# JVS.net
KiCad netlist of a schematic drawn in EAGLE
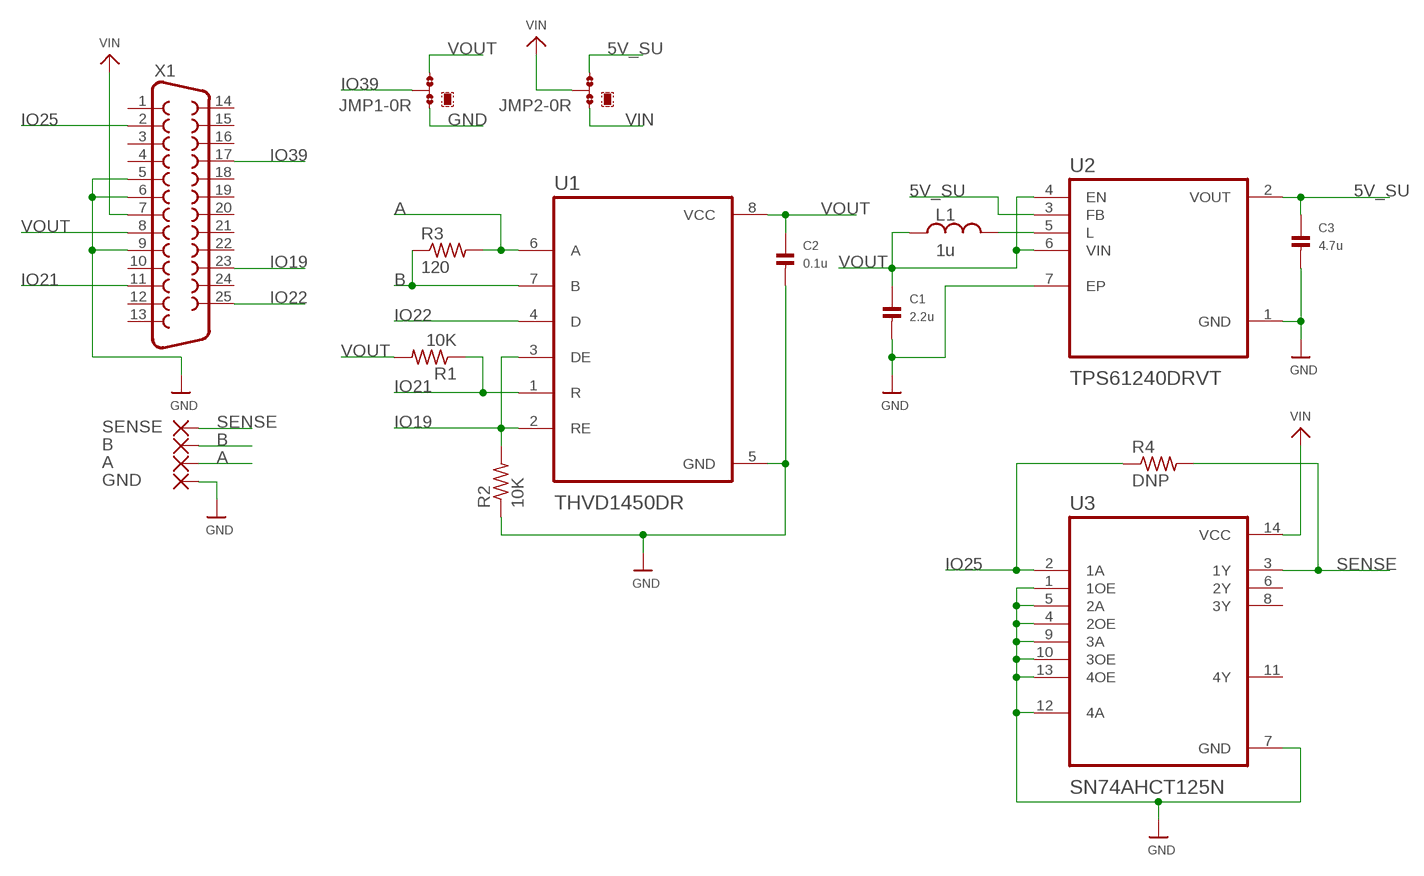
[diagram p0: schematic, sheet 1]

(export (version "E")
  (design (tool "Eeschema 10.0.6"))
  (components
    (comp (ref "A")
      (value "SMD5")
      (footprint "eagle-import:SMD2,54-5,08")
      (libsource (lib "eagle-import") (part "SMD5"))
    )
    (comp (ref "B")
      (value "SMD5")
      (footprint "eagle-import:SMD2,54-5,08")
      (libsource (lib "eagle-import") (part "SMD5"))
    )
    (comp (ref "C1")
      (value "2.2u")
      (footprint "eagle-import:1206")
      (libsource (lib "eagle-import") (part "CAP_CERAMIC1206"))
    )
    (comp (ref "C2")
      (value "0.1u")
      (footprint "eagle-import:1206")
      (libsource (lib "eagle-import") (part "CAP_CERAMIC1206"))
    )
    (comp (ref "C3")
      (value "4.7u")
      (footprint "eagle-import:1206")
      (libsource (lib "eagle-import") (part "CAP_CERAMIC1206"))
    )
    (comp (ref "GND")
      (value "SMD5")
      (footprint "eagle-import:SMD2,54-5,08")
      (libsource (lib "eagle-import") (part "SMD5"))
    )
    (comp (ref "JMP1")
      (value "0R-JUMPA")
      (footprint "eagle-import:A0R-JMP")
      (libsource (lib "eagle-import") (part "0R-JUMPA"))
    )
    (comp (ref "JMP2")
      (value "0R-JUMPA")
      (footprint "eagle-import:A0R-JMP")
      (libsource (lib "eagle-import") (part "0R-JUMPA"))
    )
    (comp (ref "L1")
      (value "1u")
      (footprint "eagle-import:INDC2009X120")
      (libsource (lib "eagle-import") (part "LCHIP-0805(2012-METRIC)_"))
    )
    (comp (ref "R1")
      (value "10K")
      (footprint "eagle-import:R1206")
      (libsource (lib "eagle-import") (part "R-US_R1206"))
    )
    (comp (ref "R2")
      (value "10K")
      (footprint "eagle-import:R1206")
      (libsource (lib "eagle-import") (part "R-US_R1206"))
    )
    (comp (ref "R3")
      (value "120")
      (footprint "eagle-import:R1206")
      (libsource (lib "eagle-import") (part "R-US_R1206"))
    )
    (comp (ref "R4")
      (value "DNP")
      (footprint "eagle-import:R1206")
      (libsource (lib "eagle-import") (part "R-US_R1206"))
    )
    (comp (ref "SENSE")
      (value "SMD5")
      (footprint "eagle-import:SMD2,54-5,08")
      (libsource (lib "eagle-import") (part "SMD5"))
    )
    (comp (ref "U1")
      (value "THVD1450DR")
      (footprint "eagle-import:SOIC127P599X175-8N")
      (fields (field (name "MF") "Texas Instruments"))
      (libsource (lib "eagle-import") (part "THVD1450DR"))
    )
    (comp (ref "U2")
      (value "TPS61240DRVT")
      (footprint "eagle-import:SON65P200X200X80-7N")
      (fields (field (name "DIGI-KEY_PART_NUMBER") "296-24519-2-ND") (field (name "MF") "Texas Instruments"))
      (libsource (lib "eagle-import") (part "TPS61240DRVT"))
    )
    (comp (ref "U3")
      (value "SN74AHCT125N")
      (footprint "eagle-import:DIP794W45P254L1969H508Q14")
      (fields (field (name "MF") "Texas Instruments"))
      (libsource (lib "eagle-import") (part "SN74AHCT125N"))
    )
    (comp (ref "X1")
      (value "DB25_FEMALEH")
      (footprint "eagle-import:F25H")
      (libsource (lib "eagle-import") (part "DB25_FEMALEH"))
    )
  )
  (nets
    (net (code "1") (name "/5V_SU") (class "Default")
      (node (ref "C3") (pin "1") (pinfunction "P$1_1") (pintype "passive"))
      (node (ref "JMP2") (pin "3") (pinfunction "3_3") (pintype "passive"))
      (node (ref "U2") (pin "2") (pinfunction "VOUT_2") (pintype "output"))
      (node (ref "U2") (pin "3") (pinfunction "FB_3") (pintype "input"))
    )
    (net (code "2") (name "/A") (class "Default")
      (node (ref "A") (pin "1") (pinfunction "P_1") (pintype "passive"))
      (node (ref "R3") (pin "2") (pinfunction "2_2") (pintype "passive"))
      (node (ref "U1") (pin "6") (pinfunction "A_6") (pintype "bidirectional"))
    )
    (net (code "3") (name "/B") (class "Default")
      (node (ref "B") (pin "1") (pinfunction "P_1") (pintype "passive"))
      (node (ref "R3") (pin "1") (pinfunction "1_1") (pintype "passive"))
      (node (ref "U1") (pin "7") (pinfunction "B_7") (pintype "bidirectional"))
    )
    (net (code "4") (name "/IO19") (class "Default")
      (node (ref "R2") (pin "2") (pinfunction "2_2") (pintype "passive"))
      (node (ref "U1") (pin "2") (pinfunction "RE_2") (pintype "bidirectional"))
      (node (ref "U1") (pin "3") (pinfunction "DE_3") (pintype "bidirectional"))
      (node (ref "X1") (pin "23") (pinfunction "23_23") (pintype "passive"))
    )
    (net (code "5") (name "/IO21") (class "Default")
      (node (ref "R1") (pin "1") (pinfunction "1_1") (pintype "passive"))
      (node (ref "U1") (pin "1") (pinfunction "R_1") (pintype "bidirectional"))
      (node (ref "X1") (pin "11") (pinfunction "11_11") (pintype "passive"))
    )
    (net (code "6") (name "/IO22") (class "Default")
      (node (ref "U1") (pin "4") (pinfunction "D_4") (pintype "bidirectional"))
      (node (ref "X1") (pin "25") (pinfunction "25_25") (pintype "passive"))
    )
    (net (code "7") (name "/IO25") (class "Default")
      (node (ref "R4") (pin "1") (pinfunction "1_1") (pintype "passive"))
      (node (ref "U3") (pin "2") (pinfunction "1A_2") (pintype "input"))
      (node (ref "X1") (pin "2") (pinfunction "2_2") (pintype "passive"))
    )
    (net (code "8") (name "/IO39") (class "Default")
      (node (ref "JMP1") (pin "2") (pinfunction "2_2") (pintype "passive"))
      (node (ref "X1") (pin "17") (pinfunction "17_17") (pintype "passive"))
    )
    (net (code "9") (name "/SENSE") (class "Default")
      (node (ref "R4") (pin "2") (pinfunction "2_2") (pintype "passive"))
      (node (ref "SENSE") (pin "1") (pinfunction "P_1") (pintype "passive"))
      (node (ref "U3") (pin "3") (pinfunction "1Y_3") (pintype "output"))
    )
    (net (code "10") (name "/VOUT") (class "Default")
      (node (ref "C1") (pin "1") (pinfunction "P$1_1") (pintype "passive"))
      (node (ref "C2") (pin "1") (pinfunction "P$1_1") (pintype "passive"))
      (node (ref "JMP1") (pin "3") (pinfunction "3_3") (pintype "passive"))
      (node (ref "L1") (pin "1") (pinfunction "1_1") (pintype "passive"))
      (node (ref "R1") (pin "2") (pinfunction "2_2") (pintype "passive"))
      (node (ref "U1") (pin "8") (pinfunction "VCC_8") (pintype "power_in"))
      (node (ref "U2") (pin "4") (pinfunction "EN_4") (pintype "input"))
      (node (ref "U2") (pin "6") (pinfunction "VIN_6") (pintype "input"))
      (node (ref "X1") (pin "8") (pinfunction "8_8") (pintype "passive"))
    )
    (net (code "11") (name "GND") (class "Default")
      (node (ref "C1") (pin "2") (pinfunction "P$2_2") (pintype "passive"))
      (node (ref "C2") (pin "2") (pinfunction "P$2_2") (pintype "passive"))
      (node (ref "C3") (pin "2") (pinfunction "P$2_2") (pintype "passive"))
      (node (ref "GND") (pin "1") (pinfunction "P_1") (pintype "passive"))
      (node (ref "JMP1") (pin "1") (pinfunction "1_1") (pintype "passive"))
      (node (ref "R2") (pin "1") (pinfunction "1_1") (pintype "passive"))
      (node (ref "U1") (pin "5") (pinfunction "GND_5") (pintype "power_in"))
      (node (ref "U2") (pin "1") (pinfunction "GND_1") (pintype "power_in"))
      (node (ref "U2") (pin "7") (pinfunction "EP_7") (pintype "bidirectional"))
      (node (ref "U3") (pin "1") (pinfunction "1OE_1") (pintype "input"))
      (node (ref "U3") (pin "10") (pinfunction "3OE_10") (pintype "input"))
      (node (ref "U3") (pin "12") (pinfunction "4A_12") (pintype "bidirectional"))
      (node (ref "U3") (pin "13") (pinfunction "4OE_13") (pintype "input"))
      (node (ref "U3") (pin "4") (pinfunction "2OE_4") (pintype "input"))
      (node (ref "U3") (pin "5") (pinfunction "2A_5") (pintype "input"))
      (node (ref "U3") (pin "7") (pinfunction "GND_7") (pintype "power_in"))
      (node (ref "U3") (pin "9") (pinfunction "3A_9") (pintype "input"))
      (node (ref "X1") (pin "5") (pinfunction "5_5") (pintype "passive"))
      (node (ref "X1") (pin "6") (pinfunction "6_6") (pintype "passive"))
      (node (ref "X1") (pin "9") (pinfunction "9_9") (pintype "passive"))
    )
    (net (code "12") (name "Net-(U2-L)") (class "Default")
      (node (ref "L1") (pin "2") (pinfunction "2_2") (pintype "passive"))
      (node (ref "U2") (pin "5") (pinfunction "L_5") (pintype "input"))
    )
    (net (code "13") (name "VIN") (class "Default")
      (node (ref "JMP2") (pin "1") (pinfunction "1_1") (pintype "passive"))
      (node (ref "JMP2") (pin "2") (pinfunction "2_2") (pintype "passive"))
      (node (ref "U3") (pin "14") (pinfunction "VCC_14") (pintype "power_in"))
      (node (ref "X1") (pin "7") (pinfunction "7_7") (pintype "passive"))
    )
    (net (code "14") (name "unconnected-(U3-2Y-Pad6)") (class "Default")
      (node (ref "U3") (pin "6") (pinfunction "2Y_6") (pintype "output"))
    )
    (net (code "15") (name "unconnected-(U3-3Y-Pad8)") (class "Default")
      (node (ref "U3") (pin "8") (pinfunction "3Y_8") (pintype "output"))
    )
    (net (code "16") (name "unconnected-(U3-4Y-Pad11)") (class "Default")
      (node (ref "U3") (pin "11") (pinfunction "4Y_11") (pintype "output"))
    )
    (net (code "17") (name "unconnected-(X1-Pad1)") (class "Default")
      (node (ref "X1") (pin "1") (pinfunction "1_1") (pintype "passive"))
    )
    (net (code "18") (name "unconnected-(X1-Pad3)") (class "Default")
      (node (ref "X1") (pin "3") (pinfunction "3_3") (pintype "passive"))
    )
    (net (code "19") (name "unconnected-(X1-Pad4)") (class "Default")
      (node (ref "X1") (pin "4") (pinfunction "4_4") (pintype "passive"))
    )
    (net (code "20") (name "unconnected-(X1-Pad10)") (class "Default")
      (node (ref "X1") (pin "10") (pinfunction "10_10") (pintype "passive"))
    )
    (net (code "21") (name "unconnected-(X1-Pad12)") (class "Default")
      (node (ref "X1") (pin "12") (pinfunction "12_12") (pintype "passive"))
    )
    (net (code "22") (name "unconnected-(X1-Pad13)") (class "Default")
      (node (ref "X1") (pin "13") (pinfunction "13_13") (pintype "passive"))
    )
    (net (code "23") (name "unconnected-(X1-Pad14)") (class "Default")
      (node (ref "X1") (pin "14") (pinfunction "14_14") (pintype "passive"))
    )
    (net (code "24") (name "unconnected-(X1-Pad15)") (class "Default")
      (node (ref "X1") (pin "15") (pinfunction "15_15") (pintype "passive"))
    )
    (net (code "25") (name "unconnected-(X1-Pad16)") (class "Default")
      (node (ref "X1") (pin "16") (pinfunction "16_16") (pintype "passive"))
    )
    (net (code "26") (name "unconnected-(X1-Pad18)") (class "Default")
      (node (ref "X1") (pin "18") (pinfunction "18_18") (pintype "passive"))
    )
    (net (code "27") (name "unconnected-(X1-Pad19)") (class "Default")
      (node (ref "X1") (pin "19") (pinfunction "19_19") (pintype "passive"))
    )
    (net (code "28") (name "unconnected-(X1-Pad20)") (class "Default")
      (node (ref "X1") (pin "20") (pinfunction "20_20") (pintype "passive"))
    )
    (net (code "29") (name "unconnected-(X1-Pad21)") (class "Default")
      (node (ref "X1") (pin "21") (pinfunction "21_21") (pintype "passive"))
    )
    (net (code "30") (name "unconnected-(X1-Pad22)") (class "Default")
      (node (ref "X1") (pin "22") (pinfunction "22_22") (pintype "passive"))
    )
    (net (code "31") (name "unconnected-(X1-Pad24)") (class "Default")
      (node (ref "X1") (pin "24") (pinfunction "24_24") (pintype "passive"))
    )
  )
)
